# tag.net
KiCad netlist of a schematic drawn in EAGLE
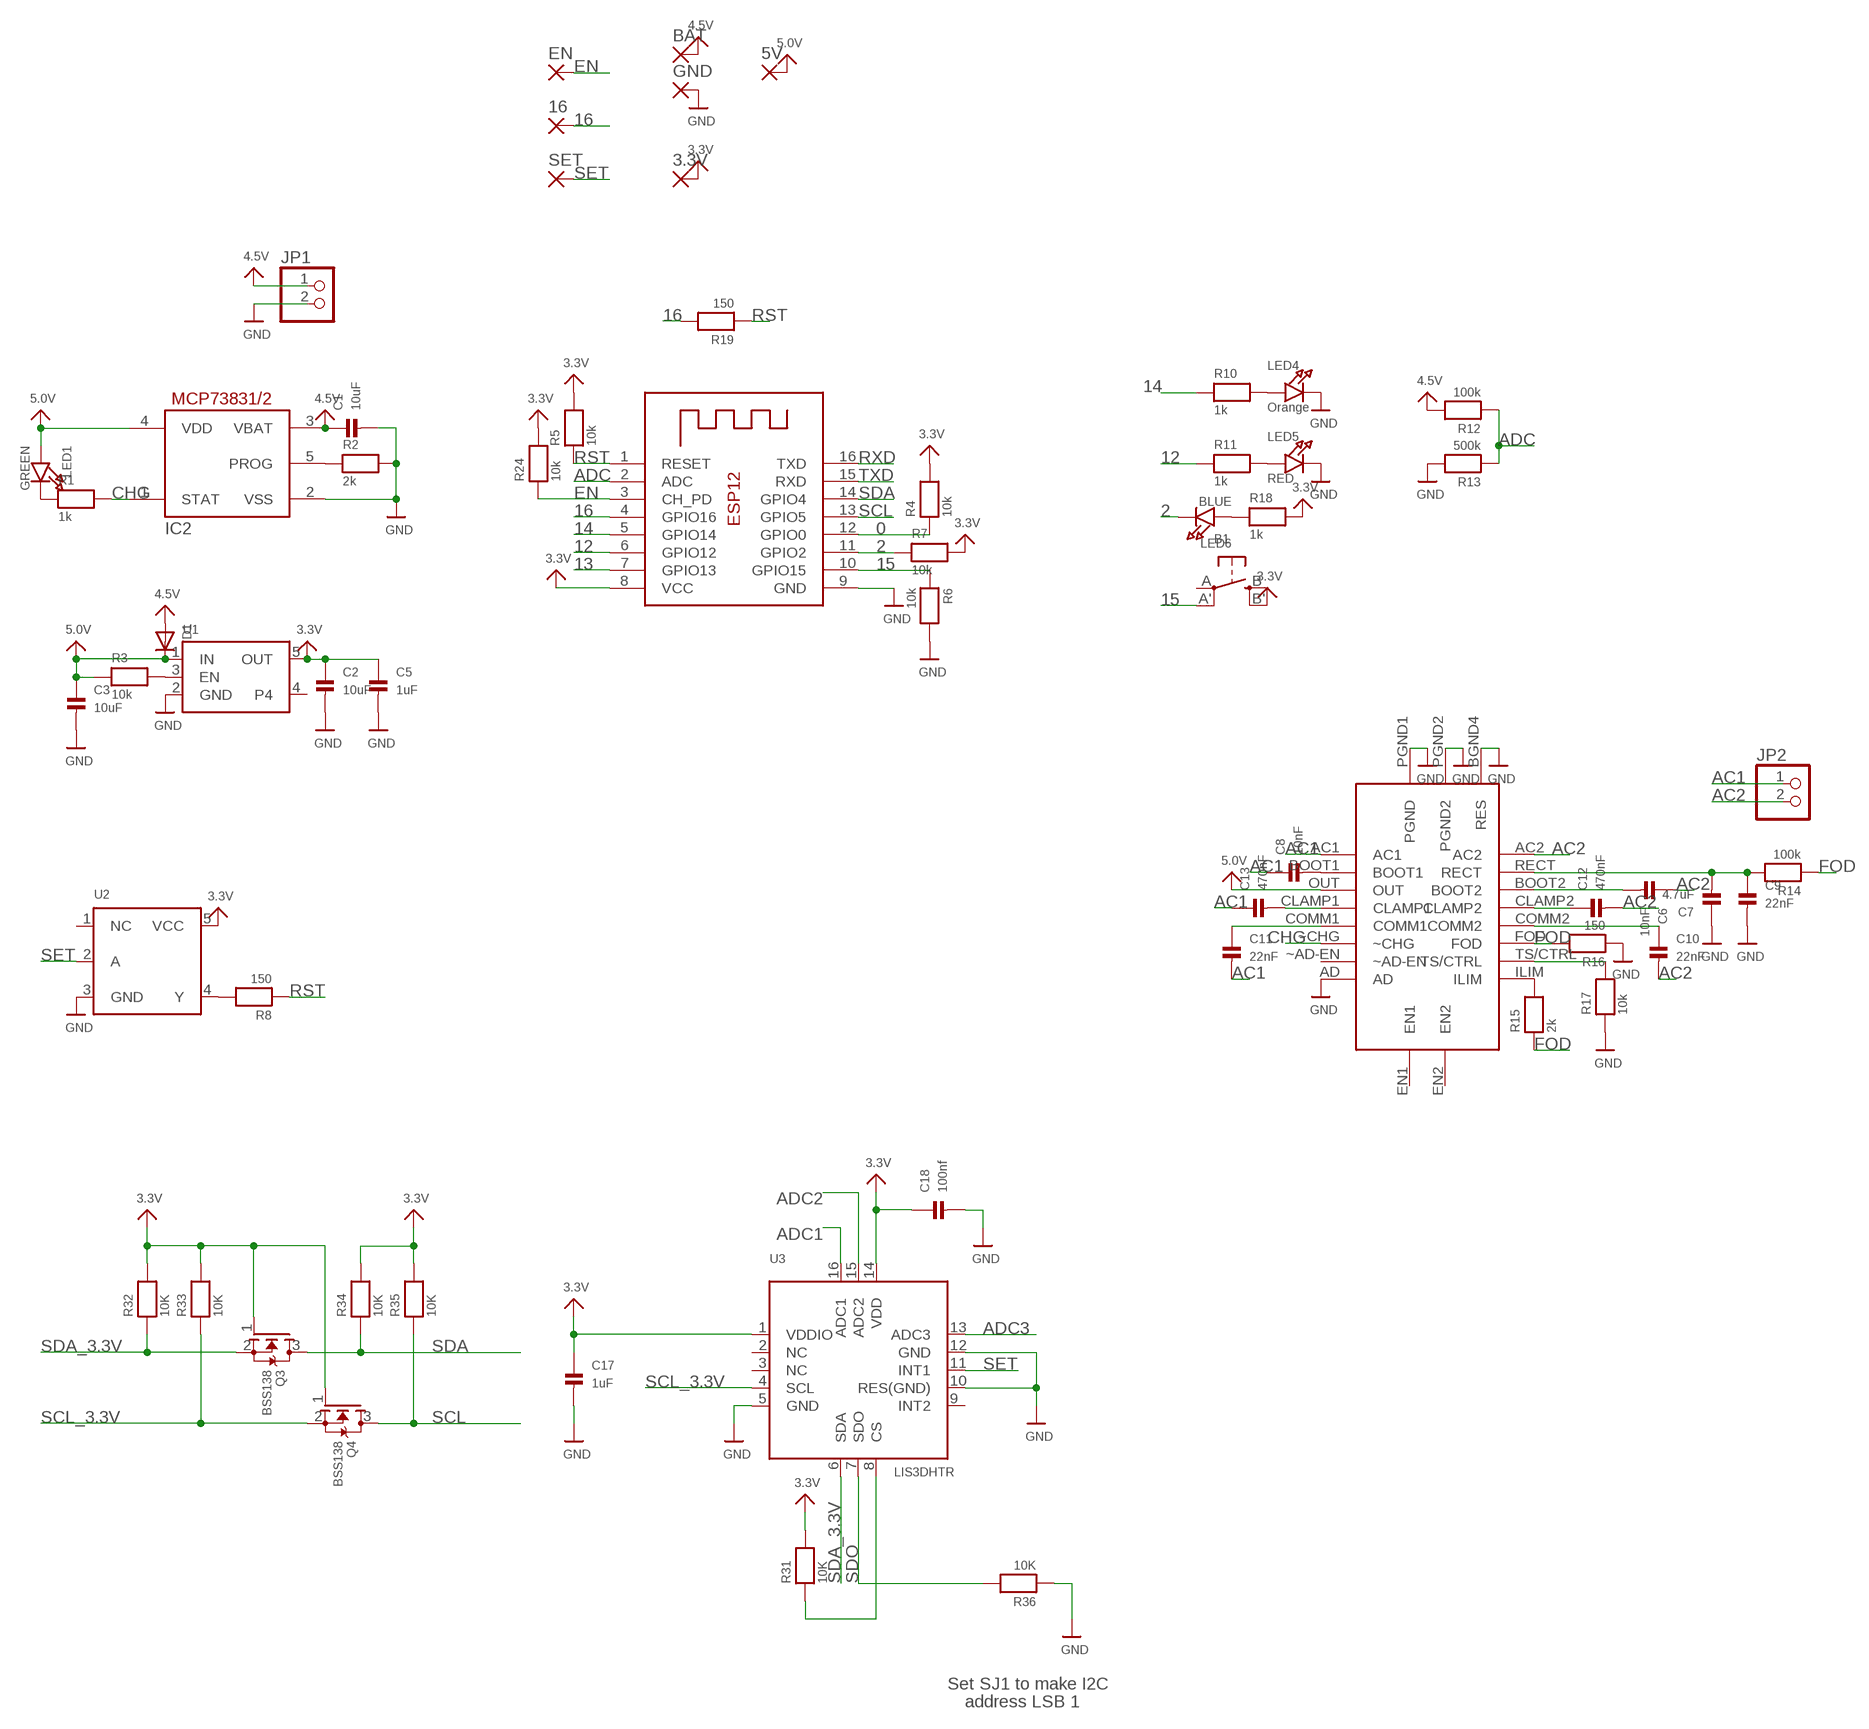
[diagram p0: schematic, sheet 1]

(export (version "E")
  (design (tool "Eeschema 10.0.6"))
  (components
    (comp (ref "3.3V")
      (value "SMD2")
      (footprint "eagle-import:SMD1,27-2,54")
      (libsource (lib "eagle-import") (part "SMD2"))
    )
    (comp (ref "5V")
      (value "SMD2")
      (footprint "eagle-import:SMD1,27-2,54")
      (libsource (lib "eagle-import") (part "SMD2"))
    )
    (comp (ref "16")
      (value "SMD2")
      (footprint "eagle-import:SMD1,27-2,54")
      (libsource (lib "eagle-import") (part "SMD2"))
    )
    (comp (ref "B1")
      (value "SWITCH_TACT_SMT4.6X2.8")
      (footprint "eagle-import:BTN_KMR2_4.6X2.8")
      (libsource (lib "eagle-import") (part "SWITCH_TACT_SMT4.6X2.8"))
    )
    (comp (ref "BAT")
      (value "SMD2")
      (footprint "eagle-import:SMD1,27-2,54")
      (libsource (lib "eagle-import") (part "SMD2"))
    )
    (comp (ref "C1")
      (value "10uF")
      (footprint "eagle-import:0603")
      (libsource (lib "eagle-import") (part "CAP_CERAMIC0603"))
    )
    (comp (ref "C2")
      (value "10uF")
      (footprint "eagle-import:0603")
      (libsource (lib "eagle-import") (part "CAP_CERAMIC0603"))
    )
    (comp (ref "C3")
      (value "10uF")
      (footprint "eagle-import:0603")
      (libsource (lib "eagle-import") (part "CAP_CERAMIC0603"))
    )
    (comp (ref "C5")
      (value "1uF")
      (footprint "eagle-import:0402")
      (libsource (lib "eagle-import") (part "CAP_CERAMIC0402"))
    )
    (comp (ref "C6")
      (value "10nF")
      (footprint "eagle-import:0402")
      (libsource (lib "eagle-import") (part "CAP_CERAMIC0402"))
    )
    (comp (ref "C7")
      (value "4.7uF")
      (footprint "eagle-import:0603")
      (libsource (lib "eagle-import") (part "CAP_CERAMIC0603"))
    )
    (comp (ref "C8")
      (value "10nF")
      (footprint "eagle-import:0402")
      (libsource (lib "eagle-import") (part "CAP_CERAMIC0402"))
    )
    (comp (ref "C9")
      (value "22nF")
      (footprint "eagle-import:0402")
      (libsource (lib "eagle-import") (part "CAP_CERAMIC0402"))
    )
    (comp (ref "C10")
      (value "22nF")
      (footprint "eagle-import:0402")
      (libsource (lib "eagle-import") (part "CAP_CERAMIC0402"))
    )
    (comp (ref "C11")
      (value "22nF")
      (footprint "eagle-import:0402")
      (libsource (lib "eagle-import") (part "CAP_CERAMIC0402"))
    )
    (comp (ref "C12")
      (value "470nF")
      (footprint "eagle-import:0402")
      (libsource (lib "eagle-import") (part "CAP_CERAMIC0402"))
    )
    (comp (ref "C13")
      (value "470nF")
      (footprint "eagle-import:0402")
      (libsource (lib "eagle-import") (part "CAP_CERAMIC0402"))
    )
    (comp (ref "C17")
      (value "1uF")
      (footprint "eagle-import:0402")
      (libsource (lib "eagle-import") (part "CAP_CERAMIC0402"))
    )
    (comp (ref "C18")
      (value "100nf")
      (footprint "eagle-import:0402")
      (libsource (lib "eagle-import") (part "CAP_CERAMIC0402"))
    )
    (comp (ref "D1")
      (value "DIODESOD-123")
      (footprint "eagle-import:SOD-123")
      (libsource (lib "eagle-import") (part "DIODESOD-123"))
    )
    (comp (ref "EN")
      (value "SMD2")
      (footprint "eagle-import:SMD1,27-2,54")
      (libsource (lib "eagle-import") (part "SMD2"))
    )
    (comp (ref "GND")
      (value "SMD2")
      (footprint "eagle-import:SMD1,27-2,54")
      (libsource (lib "eagle-import") (part "SMD2"))
    )
    (comp (ref "IC2")
      (value "MCP73831/OT")
      (footprint "eagle-import:SOT23-5L")
      (libsource (lib "eagle-import") (part "MCP73831/OT"))
    )
    (comp (ref "JP1")
      (value "HEADER-1X2")
      (footprint "eagle-import:1X02_OVAL")
      (libsource (lib "eagle-import") (part "HEADER-1X2"))
    )
    (comp (ref "JP2")
      (value "HEADER-1X2")
      (footprint "eagle-import:1X02_OVAL")
      (libsource (lib "eagle-import") (part "HEADER-1X2"))
    )
    (comp (ref "LED1")
      (value "GREEN")
      (footprint "eagle-import:CHIPLED_0603")
      (libsource (lib "eagle-import") (part "LED0603"))
    )
    (comp (ref "LED4")
      (value "Orange")
      (footprint "eagle-import:CHIPLED_0603")
      (libsource (lib "eagle-import") (part "LED0603"))
    )
    (comp (ref "LED5")
      (value "RED")
      (footprint "eagle-import:CHIPLED_0603")
      (libsource (lib "eagle-import") (part "LED0603"))
    )
    (comp (ref "LED6")
      (value "BLUE")
      (footprint "eagle-import:CHIPLED_0603")
      (libsource (lib "eagle-import") (part "LED0603"))
    )
    (comp (ref "Q3")
      (value "BSS138")
      (footprint "eagle-import:SOT23-WIDE")
      (libsource (lib "eagle-import") (part "MOSFET-NWIDE"))
    )
    (comp (ref "Q4")
      (value "BSS138")
      (footprint "eagle-import:SOT23-WIDE")
      (libsource (lib "eagle-import") (part "MOSFET-NWIDE"))
    )
    (comp (ref "R1")
      (value "1k")
      (footprint "eagle-import:0402")
      (libsource (lib "eagle-import") (part "RESISTOR0402"))
    )
    (comp (ref "R2")
      (value "2k")
      (footprint "eagle-import:0402")
      (libsource (lib "eagle-import") (part "RESISTOR0402"))
    )
    (comp (ref "R3")
      (value "10k")
      (footprint "eagle-import:0402")
      (libsource (lib "eagle-import") (part "RESISTOR0402"))
    )
    (comp (ref "R4")
      (value "10k")
      (footprint "eagle-import:0402")
      (libsource (lib "eagle-import") (part "RESISTOR0402"))
    )
    (comp (ref "R5")
      (value "10k")
      (footprint "eagle-import:0402")
      (libsource (lib "eagle-import") (part "RESISTOR0402"))
    )
    (comp (ref "R6")
      (value "10k")
      (footprint "eagle-import:0402")
      (libsource (lib "eagle-import") (part "RESISTOR0402"))
    )
    (comp (ref "R7")
      (value "10k")
      (footprint "eagle-import:0402")
      (libsource (lib "eagle-import") (part "RESISTOR0402"))
    )
    (comp (ref "R8")
      (value "150")
      (footprint "eagle-import:0402")
      (libsource (lib "eagle-import") (part "RESISTOR0402"))
    )
    (comp (ref "R10")
      (value "1k")
      (footprint "eagle-import:0402")
      (libsource (lib "eagle-import") (part "RESISTOR0402"))
    )
    (comp (ref "R11")
      (value "1k")
      (footprint "eagle-import:0402")
      (libsource (lib "eagle-import") (part "RESISTOR0402"))
    )
    (comp (ref "R12")
      (value "100k")
      (footprint "eagle-import:0402")
      (libsource (lib "eagle-import") (part "RESISTOR0402"))
    )
    (comp (ref "R13")
      (value "500k")
      (footprint "eagle-import:0402")
      (libsource (lib "eagle-import") (part "RESISTOR0402"))
    )
    (comp (ref "R14")
      (value "100k")
      (footprint "eagle-import:0402")
      (libsource (lib "eagle-import") (part "RESISTOR0402"))
    )
    (comp (ref "R15")
      (value "2k")
      (footprint "eagle-import:0402")
      (libsource (lib "eagle-import") (part "RESISTOR0402"))
    )
    (comp (ref "R16")
      (value "150")
      (footprint "eagle-import:0402")
      (libsource (lib "eagle-import") (part "RESISTOR0402"))
    )
    (comp (ref "R17")
      (value "10k")
      (footprint "eagle-import:0402")
      (libsource (lib "eagle-import") (part "RESISTOR0402"))
    )
    (comp (ref "R18")
      (value "1k")
      (footprint "eagle-import:0402")
      (libsource (lib "eagle-import") (part "RESISTOR0402"))
    )
    (comp (ref "R19")
      (value "150")
      (footprint "eagle-import:0402")
      (libsource (lib "eagle-import") (part "RESISTOR0402"))
    )
    (comp (ref "R24")
      (value "10k")
      (footprint "eagle-import:0402")
      (libsource (lib "eagle-import") (part "RESISTOR0402"))
    )
    (comp (ref "R31")
      (value "10K")
      (footprint "eagle-import:0402")
      (libsource (lib "eagle-import") (part "RESISTOR0402"))
    )
    (comp (ref "R32")
      (value "10K")
      (footprint "eagle-import:0402")
      (libsource (lib "eagle-import") (part "RESISTOR0402"))
    )
    (comp (ref "R33")
      (value "10K")
      (footprint "eagle-import:0402")
      (libsource (lib "eagle-import") (part "RESISTOR0402"))
    )
    (comp (ref "R34")
      (value "10K")
      (footprint "eagle-import:0402")
      (libsource (lib "eagle-import") (part "RESISTOR0402"))
    )
    (comp (ref "R35")
      (value "10K")
      (footprint "eagle-import:0402")
      (libsource (lib "eagle-import") (part "RESISTOR0402"))
    )
    (comp (ref "R36")
      (value "10K")
      (footprint "eagle-import:0402")
      (libsource (lib "eagle-import") (part "RESISTOR0402"))
    )
    (comp (ref "SET")
      (value "SMD2")
      (footprint "eagle-import:SMD1,27-2,54")
      (libsource (lib "eagle-import") (part "SMD2"))
    )
    (comp (ref "U$1")
      (value "BQ51013B")
      (footprint "eagle-import:VQFN")
      (libsource (lib "eagle-import") (part "BQ51013B"))
    )
    (comp (ref "U1")
      (value "VREG_SOT23-5")
      (footprint "eagle-import:SOT23-5")
      (libsource (lib "eagle-import") (part "VREG_SOT23-5"))
    )
    (comp (ref "U2")
      (value "74LVC1G04")
      (footprint "eagle-import:SOT23-5")
      (libsource (lib "eagle-import") (part "74LVC1G04"))
    )
    (comp (ref "U3")
      (value "LIS3DHTR")
      (footprint "eagle-import:LGA16_3X3MM")
      (libsource (lib "eagle-import") (part "ACCEL_LIS3DHTR"))
    )
    (comp (ref "X1")
      (value "ESP-12")
      (footprint "eagle-import:ESP-12")
      (libsource (lib "eagle-import") (part "ESP-12"))
    )
  )
  (nets
    (net (code "1") (name "/0") (class "Default")
      (node (ref "R4") (pin "1") (pinfunction "1_1") (pintype "passive"))
      (node (ref "X1") (pin "12") (pinfunction "GPIO0_12") (pintype "bidirectional"))
    )
    (net (code "2") (name "/2") (class "Default")
      (node (ref "LED6") (pin "C") (pinfunction "C_C") (pintype "passive"))
      (node (ref "R7") (pin "1") (pinfunction "1_1") (pintype "passive"))
      (node (ref "X1") (pin "11") (pinfunction "GPIO2_11") (pintype "bidirectional"))
    )
    (net (code "3") (name "/12") (class "Default")
      (node (ref "R11") (pin "1") (pinfunction "1_1") (pintype "passive"))
      (node (ref "X1") (pin "6") (pinfunction "GPIO12_6") (pintype "bidirectional"))
    )
    (net (code "4") (name "/13") (class "Default")
      (node (ref "X1") (pin "7") (pinfunction "GPIO13_7") (pintype "bidirectional"))
    )
    (net (code "5") (name "/14") (class "Default")
      (node (ref "R10") (pin "1") (pinfunction "1_1") (pintype "passive"))
      (node (ref "X1") (pin "5") (pinfunction "GPIO14_5") (pintype "bidirectional"))
    )
    (net (code "6") (name "/15") (class "Default")
      (node (ref "B1") (pin "A'") (pinfunction "P1_A'") (pintype "passive"))
      (node (ref "R6") (pin "1") (pinfunction "1_1") (pintype "passive"))
      (node (ref "X1") (pin "10") (pinfunction "GPIO15_10") (pintype "bidirectional"))
    )
    (net (code "7") (name "/16") (class "Default")
      (node (ref "16") (pin "1") (pinfunction "P_1") (pintype "passive"))
      (node (ref "R19") (pin "2") (pinfunction "2_2") (pintype "passive"))
      (node (ref "X1") (pin "4") (pinfunction "GPIO16_4") (pintype "bidirectional"))
    )
    (net (code "8") (name "/AC1") (class "Default")
      (node (ref "C11") (pin "2") (pinfunction "P$2_2") (pintype "passive"))
      (node (ref "C13") (pin "1") (pinfunction "P$1_1") (pintype "passive"))
      (node (ref "C8") (pin "1") (pinfunction "P$1_1") (pintype "passive"))
      (node (ref "JP2") (pin "1") (pinfunction "1_1") (pintype "passive"))
      (node (ref "U$1") (pin "AC1") (pinfunction "AC1_AC1") (pintype "bidirectional"))
    )
    (net (code "9") (name "/AC2") (class "Default")
      (node (ref "C10") (pin "2") (pinfunction "P$2_2") (pintype "passive"))
      (node (ref "C12") (pin "2") (pinfunction "P$2_2") (pintype "passive"))
      (node (ref "C6") (pin "1") (pinfunction "P$1_1") (pintype "passive"))
      (node (ref "JP2") (pin "2") (pinfunction "2_2") (pintype "passive"))
      (node (ref "U$1") (pin "AC2") (pinfunction "AC2_AC2") (pintype "bidirectional"))
    )
    (net (code "10") (name "/ADC") (class "Default")
      (node (ref "R12") (pin "1") (pinfunction "1_1") (pintype "passive"))
      (node (ref "R13") (pin "1") (pinfunction "1_1") (pintype "passive"))
      (node (ref "X1") (pin "2") (pinfunction "ADC_2") (pintype "passive"))
    )
    (net (code "11") (name "/ADC1") (class "Default")
      (node (ref "U3") (pin "16") (pinfunction "ADC1_16") (pintype "input"))
    )
    (net (code "12") (name "/ADC2") (class "Default")
      (node (ref "U3") (pin "15") (pinfunction "ADC2_15") (pintype "input"))
    )
    (net (code "13") (name "/ADC3") (class "Default")
      (node (ref "U3") (pin "13") (pinfunction "ADC3_13") (pintype "input"))
    )
    (net (code "14") (name "/CHG") (class "Default")
      (node (ref "IC2") (pin "1") (pinfunction "STAT_1") (pintype "output"))
      (node (ref "R1") (pin "2") (pinfunction "2_2") (pintype "passive"))
      (node (ref "U$1") (pin "~CHG") (pinfunction "~{CHG}_~CHG") (pintype "bidirectional"))
    )
    (net (code "15") (name "/EN") (class "Default")
      (node (ref "EN") (pin "1") (pinfunction "P_1") (pintype "passive"))
      (node (ref "R24") (pin "1") (pinfunction "1_1") (pintype "passive"))
      (node (ref "X1") (pin "3") (pinfunction "CH_PD_3") (pintype "input"))
    )
    (net (code "16") (name "/FOD") (class "Default")
      (node (ref "R14") (pin "1") (pinfunction "1_1") (pintype "passive"))
      (node (ref "R15") (pin "1") (pinfunction "1_1") (pintype "passive"))
      (node (ref "R16") (pin "2") (pinfunction "2_2") (pintype "passive"))
      (node (ref "U$1") (pin "FOD") (pinfunction "FOD_FOD") (pintype "bidirectional"))
    )
    (net (code "17") (name "/RST") (class "Default")
      (node (ref "R19") (pin "1") (pinfunction "1_1") (pintype "passive"))
      (node (ref "R5") (pin "1") (pinfunction "1_1") (pintype "passive"))
      (node (ref "R8") (pin "1") (pinfunction "1_1") (pintype "passive"))
      (node (ref "X1") (pin "1") (pinfunction "RESET_1") (pintype "input"))
    )
    (net (code "18") (name "/RXD") (class "Default")
      (node (ref "X1") (pin "16") (pinfunction "TXD_16") (pintype "output"))
    )
    (net (code "19") (name "/SCL") (class "Default")
      (node (ref "Q4") (pin "3") (pinfunction "D_3") (pintype "bidirectional"))
      (node (ref "R35") (pin "1") (pinfunction "1_1") (pintype "passive"))
      (node (ref "X1") (pin "13") (pinfunction "GPIO5_13") (pintype "bidirectional"))
    )
    (net (code "20") (name "/SCL_3.3V") (class "Default")
      (node (ref "Q4") (pin "2") (pinfunction "S_2") (pintype "bidirectional"))
      (node (ref "R33") (pin "1") (pinfunction "1_1") (pintype "passive"))
      (node (ref "U3") (pin "4") (pinfunction "SCL_4") (pintype "bidirectional"))
    )
    (net (code "21") (name "/SDA") (class "Default")
      (node (ref "Q3") (pin "3") (pinfunction "D_3") (pintype "bidirectional"))
      (node (ref "R34") (pin "1") (pinfunction "1_1") (pintype "passive"))
      (node (ref "X1") (pin "14") (pinfunction "GPIO4_14") (pintype "bidirectional"))
    )
    (net (code "22") (name "/SDA_3.3V") (class "Default")
      (node (ref "Q3") (pin "2") (pinfunction "S_2") (pintype "bidirectional"))
      (node (ref "R32") (pin "1") (pinfunction "1_1") (pintype "passive"))
      (node (ref "U3") (pin "6") (pinfunction "SDA_6") (pintype "bidirectional"))
    )
    (net (code "23") (name "/SDO") (class "Default")
      (node (ref "R36") (pin "2") (pinfunction "2_2") (pintype "passive"))
      (node (ref "U3") (pin "7") (pinfunction "SDO_7") (pintype "bidirectional"))
    )
    (net (code "24") (name "/SET") (class "Default")
      (node (ref "SET") (pin "1") (pinfunction "P_1") (pintype "passive"))
      (node (ref "U2") (pin "2") (pinfunction "A_2") (pintype "bidirectional"))
      (node (ref "U3") (pin "11") (pinfunction "INT1_11") (pintype "output"))
    )
    (net (code "25") (name "/TXD") (class "Default")
      (node (ref "X1") (pin "15") (pinfunction "RXD_15") (pintype "input"))
    )
    (net (code "26") (name "3.3V") (class "Default")
      (node (ref "3.3V") (pin "1") (pinfunction "P_1") (pintype "passive"))
      (node (ref "B1") (pin "B'") (pinfunction "S1_B'") (pintype "passive"))
      (node (ref "C17") (pin "1") (pinfunction "P$1_1") (pintype "passive"))
      (node (ref "C18") (pin "1") (pinfunction "P$1_1") (pintype "passive"))
      (node (ref "C2") (pin "1") (pinfunction "P$1_1") (pintype "passive"))
      (node (ref "C5") (pin "1") (pinfunction "P$1_1") (pintype "passive"))
      (node (ref "Q3") (pin "1") (pinfunction "G_1") (pintype "bidirectional"))
      (node (ref "Q4") (pin "1") (pinfunction "G_1") (pintype "bidirectional"))
      (node (ref "R18") (pin "2") (pinfunction "2_2") (pintype "passive"))
      (node (ref "R24") (pin "2") (pinfunction "2_2") (pintype "passive"))
      (node (ref "R31") (pin "2") (pinfunction "2_2") (pintype "passive"))
      (node (ref "R32") (pin "2") (pinfunction "2_2") (pintype "passive"))
      (node (ref "R33") (pin "2") (pinfunction "2_2") (pintype "passive"))
      (node (ref "R34") (pin "2") (pinfunction "2_2") (pintype "passive"))
      (node (ref "R35") (pin "2") (pinfunction "2_2") (pintype "passive"))
      (node (ref "R4") (pin "2") (pinfunction "2_2") (pintype "passive"))
      (node (ref "R5") (pin "2") (pinfunction "2_2") (pintype "passive"))
      (node (ref "R7") (pin "2") (pinfunction "2_2") (pintype "passive"))
      (node (ref "U1") (pin "5") (pinfunction "OUT_5") (pintype "bidirectional"))
      (node (ref "U2") (pin "5") (pinfunction "VCC_5") (pintype "power_in"))
      (node (ref "U3") (pin "1") (pinfunction "VDDIO_1") (pintype "power_in"))
      (node (ref "U3") (pin "14") (pinfunction "VDD_14") (pintype "power_in"))
      (node (ref "X1") (pin "8") (pinfunction "VCC_8") (pintype "power_in"))
    )
    (net (code "27") (name "4.5V") (class "Default")
      (node (ref "BAT") (pin "1") (pinfunction "P_1") (pintype "passive"))
      (node (ref "C1") (pin "1") (pinfunction "P$1_1") (pintype "passive"))
      (node (ref "D1") (pin "A") (pinfunction "A_A") (pintype "passive"))
      (node (ref "IC2") (pin "3") (pinfunction "VBAT_3") (pintype "bidirectional"))
      (node (ref "JP1") (pin "1") (pinfunction "1_1") (pintype "passive"))
      (node (ref "R12") (pin "2") (pinfunction "2_2") (pintype "passive"))
    )
    (net (code "28") (name "5.0V") (class "Default")
      (node (ref "5V") (pin "1") (pinfunction "P_1") (pintype "passive"))
      (node (ref "C3") (pin "1") (pinfunction "P$1_1") (pintype "passive"))
      (node (ref "D1") (pin "C") (pinfunction "C_C") (pintype "passive"))
      (node (ref "IC2") (pin "4") (pinfunction "VDD_4") (pintype "power_in"))
      (node (ref "LED1") (pin "A") (pinfunction "A_A") (pintype "passive"))
      (node (ref "R3") (pin "1") (pinfunction "1_1") (pintype "passive"))
      (node (ref "U$1") (pin "OUT") (pinfunction "OUT_OUT") (pintype "bidirectional"))
      (node (ref "U1") (pin "1") (pinfunction "IN_1") (pintype "bidirectional"))
    )
    (net (code "29") (name "GND") (class "Default")
      (node (ref "C1") (pin "2") (pinfunction "P$2_2") (pintype "passive"))
      (node (ref "C17") (pin "2") (pinfunction "P$2_2") (pintype "passive"))
      (node (ref "C18") (pin "2") (pinfunction "P$2_2") (pintype "passive"))
      (node (ref "C2") (pin "2") (pinfunction "P$2_2") (pintype "passive"))
      (node (ref "C3") (pin "2") (pinfunction "P$2_2") (pintype "passive"))
      (node (ref "C5") (pin "2") (pinfunction "P$2_2") (pintype "passive"))
      (node (ref "C7") (pin "1") (pinfunction "P$1_1") (pintype "passive"))
      (node (ref "C9") (pin "2") (pinfunction "P$2_2") (pintype "passive"))
      (node (ref "GND") (pin "1") (pinfunction "P_1") (pintype "passive"))
      (node (ref "IC2") (pin "2") (pinfunction "VSS_2") (pintype "power_in"))
      (node (ref "JP1") (pin "2") (pinfunction "2_2") (pintype "passive"))
      (node (ref "LED4") (pin "C") (pinfunction "C_C") (pintype "passive"))
      (node (ref "LED5") (pin "C") (pinfunction "C_C") (pintype "passive"))
      (node (ref "R13") (pin "2") (pinfunction "2_2") (pintype "passive"))
      (node (ref "R16") (pin "1") (pinfunction "1_1") (pintype "passive"))
      (node (ref "R17") (pin "1") (pinfunction "1_1") (pintype "passive"))
      (node (ref "R2") (pin "2") (pinfunction "2_2") (pintype "passive"))
      (node (ref "R36") (pin "1") (pinfunction "1_1") (pintype "passive"))
      (node (ref "R6") (pin "2") (pinfunction "2_2") (pintype "passive"))
      (node (ref "U$1") (pin "AD") (pinfunction "AD_AD") (pintype "bidirectional"))
      (node (ref "U$1") (pin "BGND4") (pinfunction "RES_BGND4") (pintype "bidirectional"))
      (node (ref "U$1") (pin "PGND1") (pinfunction "PGND_PGND1") (pintype "bidirectional"))
      (node (ref "U$1") (pin "PGND2") (pinfunction "PGND2_PGND2") (pintype "bidirectional"))
      (node (ref "U1") (pin "2") (pinfunction "GND_2") (pintype "bidirectional"))
      (node (ref "U2") (pin "3") (pinfunction "GND_3") (pintype "power_in"))
      (node (ref "U3") (pin "10") (pinfunction "RES(GND)_10") (pintype "bidirectional"))
      (node (ref "U3") (pin "12") (pinfunction "GND_12") (pintype "power_in"))
      (node (ref "U3") (pin "5") (pinfunction "GND_5") (pintype "power_in"))
      (node (ref "X1") (pin "9") (pinfunction "GND_9") (pintype "power_in"))
    )
    (net (code "30") (name "Net-(C6-P$2)") (class "Default")
      (node (ref "C6") (pin "2") (pinfunction "P$2_2") (pintype "passive"))
      (node (ref "U$1") (pin "BOOT2") (pinfunction "BOOT2_BOOT2") (pintype "bidirectional"))
    )
    (net (code "31") (name "Net-(C7-P$2)") (class "Default")
      (node (ref "C7") (pin "2") (pinfunction "P$2_2") (pintype "passive"))
      (node (ref "C9") (pin "1") (pinfunction "P$1_1") (pintype "passive"))
      (node (ref "R14") (pin "2") (pinfunction "2_2") (pintype "passive"))
      (node (ref "U$1") (pin "RECT") (pinfunction "RECT_RECT") (pintype "bidirectional"))
    )
    (net (code "32") (name "Net-(C8-P$2)") (class "Default")
      (node (ref "C8") (pin "2") (pinfunction "P$2_2") (pintype "passive"))
      (node (ref "U$1") (pin "BOOT1") (pinfunction "BOOT1_BOOT1") (pintype "bidirectional"))
    )
    (net (code "33") (name "Net-(C10-P$1)") (class "Default")
      (node (ref "C10") (pin "1") (pinfunction "P$1_1") (pintype "passive"))
      (node (ref "U$1") (pin "COMM2") (pinfunction "COMM2_COMM2") (pintype "bidirectional"))
    )
    (net (code "34") (name "Net-(C11-P$1)") (class "Default")
      (node (ref "C11") (pin "1") (pinfunction "P$1_1") (pintype "passive"))
      (node (ref "U$1") (pin "COMM1") (pinfunction "COMM1_COMM1") (pintype "bidirectional"))
    )
    (net (code "35") (name "Net-(C12-P$1)") (class "Default")
      (node (ref "C12") (pin "1") (pinfunction "P$1_1") (pintype "passive"))
      (node (ref "U$1") (pin "CLAMP2") (pinfunction "CLAMP2_CLAMP2") (pintype "bidirectional"))
    )
    (net (code "36") (name "Net-(C13-P$2)") (class "Default")
      (node (ref "C13") (pin "2") (pinfunction "P$2_2") (pintype "passive"))
      (node (ref "U$1") (pin "CLAMP1") (pinfunction "CLAMP1_CLAMP1") (pintype "bidirectional"))
    )
    (net (code "37") (name "Net-(IC2-PROG)") (class "Default")
      (node (ref "IC2") (pin "5") (pinfunction "PROG_5") (pintype "input"))
      (node (ref "R2") (pin "1") (pinfunction "1_1") (pintype "passive"))
    )
    (net (code "38") (name "Net-(LED1-PadC)") (class "Default")
      (node (ref "LED1") (pin "C") (pinfunction "C_C") (pintype "passive"))
      (node (ref "R1") (pin "1") (pinfunction "1_1") (pintype "passive"))
    )
    (net (code "39") (name "Net-(LED4-PadA)") (class "Default")
      (node (ref "LED4") (pin "A") (pinfunction "A_A") (pintype "passive"))
      (node (ref "R10") (pin "2") (pinfunction "2_2") (pintype "passive"))
    )
    (net (code "40") (name "Net-(LED5-PadA)") (class "Default")
      (node (ref "LED5") (pin "A") (pinfunction "A_A") (pintype "passive"))
      (node (ref "R11") (pin "2") (pinfunction "2_2") (pintype "passive"))
    )
    (net (code "41") (name "Net-(LED6-PadA)") (class "Default")
      (node (ref "LED6") (pin "A") (pinfunction "A_A") (pintype "passive"))
      (node (ref "R18") (pin "1") (pinfunction "1_1") (pintype "passive"))
    )
    (net (code "42") (name "Net-(R15-Pad2)") (class "Default")
      (node (ref "R15") (pin "2") (pinfunction "2_2") (pintype "passive"))
      (node (ref "U$1") (pin "ILIM") (pinfunction "ILIM_ILIM") (pintype "bidirectional"))
    )
    (net (code "43") (name "Net-(R17-Pad2)") (class "Default")
      (node (ref "R17") (pin "2") (pinfunction "2_2") (pintype "passive"))
      (node (ref "U$1") (pin "TS/CTRL") (pinfunction "TS/CTRL_TS/CTRL") (pintype "bidirectional"))
    )
    (net (code "44") (name "Net-(U1-EN)") (class "Default")
      (node (ref "R3") (pin "2") (pinfunction "2_2") (pintype "passive"))
      (node (ref "U1") (pin "3") (pinfunction "EN_3") (pintype "bidirectional"))
    )
    (net (code "45") (name "Net-(U2-Y)") (class "Default")
      (node (ref "R8") (pin "2") (pinfunction "2_2") (pintype "passive"))
      (node (ref "U2") (pin "4") (pinfunction "Y_4") (pintype "bidirectional"))
    )
    (net (code "46") (name "Net-(U3-CS)") (class "Default")
      (node (ref "R31") (pin "1") (pinfunction "1_1") (pintype "passive"))
      (node (ref "U3") (pin "8") (pinfunction "CS_8") (pintype "input"))
    )
    (net (code "47") (name "unconnected-(B1-P-PadA)") (class "Default")
      (node (ref "B1") (pin "A") (pinfunction "P_A") (pintype "passive"))
    )
    (net (code "48") (name "unconnected-(B1-S-PadB)") (class "Default")
      (node (ref "B1") (pin "B") (pinfunction "S_B") (pintype "passive"))
    )
    (net (code "49") (name "unconnected-(U$1-PadEN1)") (class "Default")
      (node (ref "U$1") (pin "EN1") (pinfunction "EN1_EN1") (pintype "bidirectional"))
    )
    (net (code "50") (name "unconnected-(U$1-PadEN2)") (class "Default")
      (node (ref "U$1") (pin "EN2") (pinfunction "EN2_EN2") (pintype "bidirectional"))
    )
    (net (code "51") (name "unconnected-(U$1-~{AD-EN}-Pad~AD-EN)") (class "Default")
      (node (ref "U$1") (pin "~AD-EN") (pinfunction "~{AD-EN}_~AD-EN") (pintype "bidirectional"))
    )
    (net (code "52") (name "unconnected-(U1-P4-Pad4)") (class "Default")
      (node (ref "U1") (pin "4") (pinfunction "P4_4") (pintype "bidirectional"))
    )
    (net (code "53") (name "unconnected-(U2-NC-Pad1)") (class "Default")
      (node (ref "U2") (pin "1") (pinfunction "NC_1") (pintype "no_connect"))
    )
    (net (code "54") (name "unconnected-(U3-INT2-Pad9)") (class "Default")
      (node (ref "U3") (pin "9") (pinfunction "INT2_9") (pintype "output"))
    )
    (net (code "55") (name "unconnected-(U3-NC-Pad2)") (class "Default")
      (node (ref "U3") (pin "2") (pinfunction "NC_2") (pintype "no_connect"))
    )
    (net (code "56") (name "unconnected-(U3-NC-Pad3)") (class "Default")
      (node (ref "U3") (pin "3") (pinfunction "NC_3") (pintype "no_connect"))
    )
  )
)
